# MainBoard.net
KiCad netlist of a schematic drawn in Altium Designer
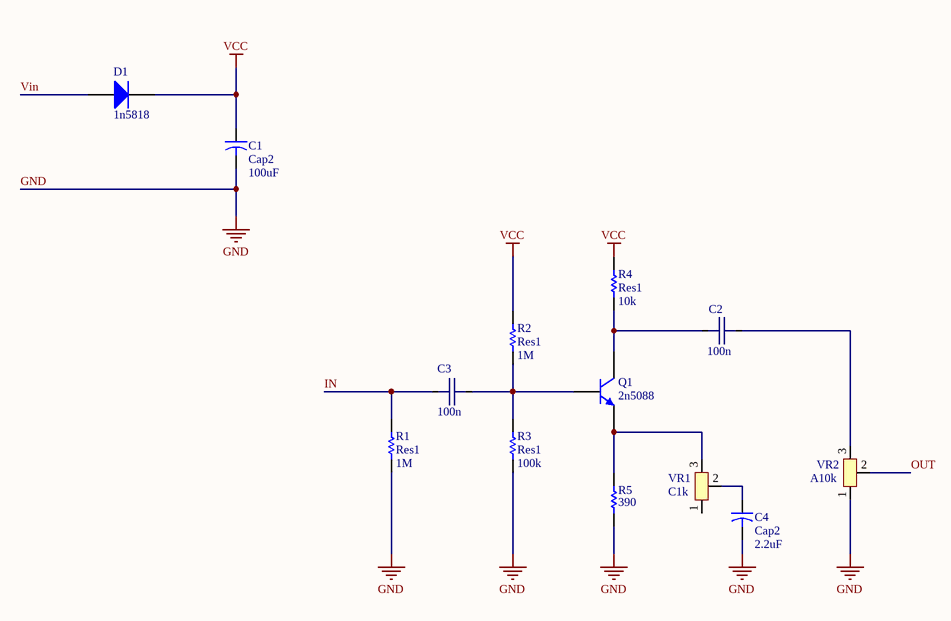
[diagram p0: MainBoard.SchDoc]

(export (version "E")
  (design (tool "Eeschema 10.0.6"))
  (components
    (comp (ref "C1")
      (value "Cap2")
      (footprint "Cap - Electrolytic")
      (description "Capacitor")
      (fields (field (name "ALTIUM_VALUE") "100uF") (field (name "PUBLISHER") "Altium Limited"))
      (libsource (lib "Miscellaneous Devices") (part "Cap2"))
    )
    (comp (ref "C2")
      (value "100n")
      (footprint "Cap-0.2\"")
      (fields (field (name "Comment") "Wima Capacitor"))
      (libsource (lib "Parts") (part "Wima Capacitor"))
    )
    (comp (ref "C3")
      (value "100n")
      (footprint "Cap-0.2\"")
      (fields (field (name "Comment") "Wima Capacitor"))
      (libsource (lib "Parts") (part "Wima Capacitor"))
    )
    (comp (ref "C4")
      (value "Cap2")
      (footprint "Cap - Electrolytic")
      (description "Capacitor")
      (fields (field (name "ALTIUM_VALUE") "2.2uF") (field (name "PUBLISHER") "Altium Limited"))
      (libsource (lib "Miscellaneous Devices") (part "Cap2"))
    )
    (comp (ref "D1")
      (value "1n5818")
      (footprint "DO-35")
      (description "High Conductance Fast Diode")
      (fields (field (name "PUBLISHER") "Altium Limited"))
      (libsource (lib "Miscellaneous Devices") (part "Diode 1N914"))
    )
    (comp (ref "Q1")
      (value "2n5088")
      (footprint "TO-226-AA")
      (description "NPN Bipolar Transistor")
      (fields (field (name "PUBLISHER") "Altium Limited"))
      (libsource (lib "Miscellaneous Devices") (part "NPN"))
    )
    (comp (ref "R1")
      (value "Res1")
      (footprint "AXIAL-0.3")
      (description "Resistor")
      (fields (field (name "ALTIUM_VALUE") "1M") (field (name "PUBLISHER") "Altium Limited"))
      (libsource (lib "Miscellaneous Devices") (part "Res1"))
    )
    (comp (ref "R2")
      (value "Res1")
      (footprint "AXIAL-0.3")
      (description "Resistor")
      (fields (field (name "ALTIUM_VALUE") "1M") (field (name "PUBLISHER") "Altium Limited"))
      (libsource (lib "Miscellaneous Devices") (part "Res1"))
    )
    (comp (ref "R3")
      (value "Res1")
      (footprint "AXIAL-0.3")
      (description "Resistor")
      (fields (field (name "ALTIUM_VALUE") "100k") (field (name "PUBLISHER") "Altium Limited"))
      (libsource (lib "Miscellaneous Devices") (part "Res1"))
    )
    (comp (ref "R4")
      (value "Res1")
      (footprint "AXIAL-0.3")
      (description "Resistor")
      (fields (field (name "ALTIUM_VALUE") "10k") (field (name "PUBLISHER") "Altium Limited"))
      (libsource (lib "Miscellaneous Devices") (part "Res1"))
    )
    (comp (ref "R5")
      (value "390")
      (footprint "AXIAL-0.3")
      (description "Resistor")
      (fields (field (name "Comment") "Res1") (field (name "PUBLISHER") "Altium Limited"))
      (libsource (lib "Miscellaneous Devices") (part "Res1"))
    )
    (comp (ref "VR1")
      (value "C1k")
      (footprint "Pot-16mm")
      (fields (field (name "Comment") "Pot-16mm"))
      (libsource (lib "Parts") (part "Pot-16mm"))
    )
    (comp (ref "VR2")
      (value "A10k")
      (footprint "Pot-16mm")
      (fields (field (name "Comment") "Pot-16mm"))
      (libsource (lib "Parts") (part "Pot-16mm"))
    )
  )
  (nets
    (net (code "1") (name "/IN") (class "Default")
      (node (ref "C3") (pin "1") (pinfunction "1_1") (pintype "passive"))
      (node (ref "R1") (pin "2") (pinfunction "2_2") (pintype "passive"))
    )
    (net (code "2") (name "/OUT") (class "Default")
      (node (ref "VR2") (pin "2") (pinfunction "2_2") (pintype "passive"))
    )
    (net (code "3") (name "/Vin") (class "Default")
      (node (ref "D1") (pin "1") (pinfunction "A_1") (pintype "passive"))
    )
    (net (code "4") (name "GND") (class "Default")
      (node (ref "C1") (pin "2") (pinfunction "2_2") (pintype "passive"))
      (node (ref "C4") (pin "2") (pinfunction "2_2") (pintype "passive"))
      (node (ref "R1") (pin "1") (pinfunction "1_1") (pintype "passive"))
      (node (ref "R3") (pin "1") (pinfunction "1_1") (pintype "passive"))
      (node (ref "R5") (pin "1") (pinfunction "1_1") (pintype "passive"))
      (node (ref "VR2") (pin "1") (pinfunction "1_1") (pintype "passive"))
    )
    (net (code "5") (name "Net-(C2-Pad2)") (class "Default")
      (node (ref "C2") (pin "2") (pinfunction "2_2") (pintype "passive"))
      (node (ref "VR2") (pin "3") (pinfunction "3_3") (pintype "passive"))
    )
    (net (code "6") (name "Net-(C4-Pad1)") (class "Default")
      (node (ref "C4") (pin "1") (pinfunction "1_1") (pintype "passive"))
      (node (ref "VR1") (pin "2") (pinfunction "2_2") (pintype "passive"))
    )
    (net (code "7") (name "Net-(Q1-B)") (class "Default")
      (node (ref "C3") (pin "2") (pinfunction "2_2") (pintype "passive"))
      (node (ref "Q1") (pin "2") (pinfunction "B_2") (pintype "passive"))
      (node (ref "R2") (pin "1") (pinfunction "1_1") (pintype "passive"))
      (node (ref "R3") (pin "2") (pinfunction "2_2") (pintype "passive"))
    )
    (net (code "8") (name "Net-(Q1-C)") (class "Default")
      (node (ref "Q1") (pin "3") (pinfunction "C_3") (pintype "passive"))
      (node (ref "R5") (pin "2") (pinfunction "2_2") (pintype "passive"))
      (node (ref "VR1") (pin "3") (pinfunction "3_3") (pintype "passive"))
    )
    (net (code "9") (name "Net-(Q1-E)") (class "Default")
      (node (ref "C2") (pin "1") (pinfunction "1_1") (pintype "passive"))
      (node (ref "Q1") (pin "1") (pinfunction "E_1") (pintype "passive"))
      (node (ref "R4") (pin "1") (pinfunction "1_1") (pintype "passive"))
    )
    (net (code "10") (name "VCC") (class "Default")
      (node (ref "C1") (pin "1") (pinfunction "1_1") (pintype "passive"))
      (node (ref "D1") (pin "2") (pinfunction "K_2") (pintype "passive"))
      (node (ref "R2") (pin "2") (pinfunction "2_2") (pintype "passive"))
      (node (ref "R4") (pin "2") (pinfunction "2_2") (pintype "passive"))
    )
    (net (code "11") (name "unconnected-(VR1-Pad1)") (class "Default")
      (node (ref "VR1") (pin "1") (pinfunction "1_1") (pintype "passive"))
    )
  )
)
